# osmo-bts-lna.net
KiCad netlist of a schematic drawn in EAGLE
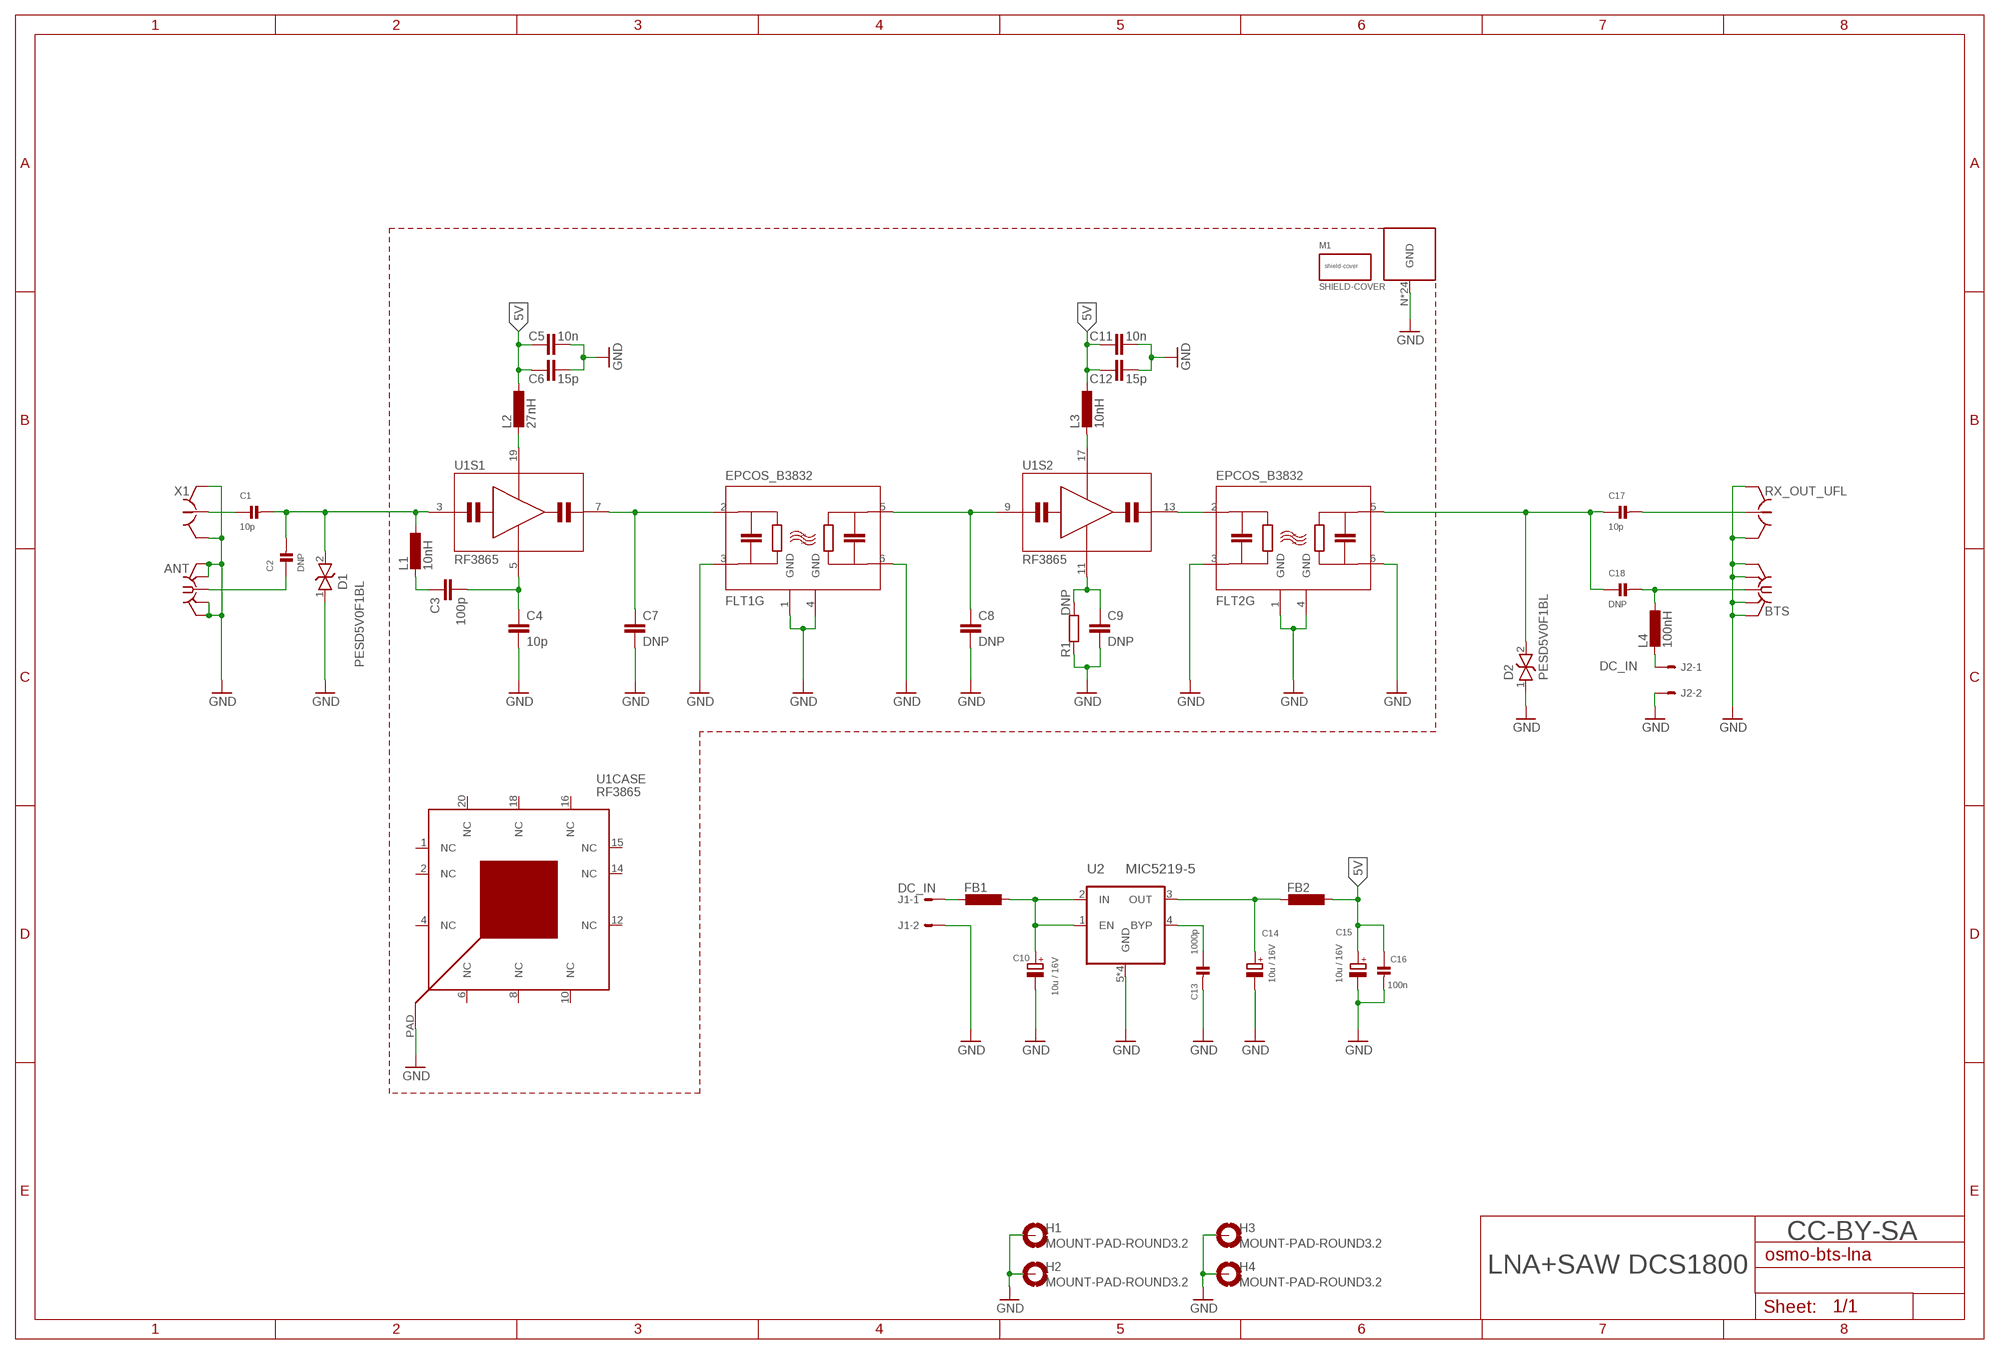
[diagram p0: schematic, sheet 1]

(export (version "E")
  (design (tool "Eeschema 10.0.6"))
  (components
    (comp (ref "ANT")
      (value "SMA-F-S-EDGE")
      (footprint "eagle-import:SMA-F-S-EDGE")
      (description "NO DESCRIPTION")
      (fields
        (field (name "MANUFACTURER") "UNKNOWN MANUFACTURER")
        (field (name "MANUFACTURERPARTNUMBER") "UNKNOWN MANUFACTURER PART NUMBER")
      )
      (libsource (lib "eagle-import") (part "SMA-F-S-EDGE"))
    )
    (comp (ref "BTS")
      (value "SMA-F-S-EDGE")
      (footprint "eagle-import:SMA-F-S-EDGE")
      (description "NO DESCRIPTION")
      (fields
        (field (name "MANUFACTURER") "UNKNOWN MANUFACTURER")
        (field (name "MANUFACTURERPARTNUMBER") "UNKNOWN MANUFACTURER PART NUMBER")
      )
      (libsource (lib "eagle-import") (part "SMA-F-S-EDGE"))
    )
    (comp (ref "C1")
      (value "10p")
      (footprint "eagle-import:_0603")
      (description "CAP CER 10PF 50V C0G/NP0 0603")
      (fields
        (field (name "MANUFACTURER") "KEMET")
        (field (name "MANUFACTURERPARTNUMBER") "C0603C100J5GACTU")
      )
      (libsource (lib "eagle-import") (part "CAP_CERAMIC_0603"))
    )
    (comp (ref "C2")
      (value "DNP")
      (footprint "eagle-import:_0603")
      (description "NO DESCRIPTION")
      (fields
        (field (name "MANUFACTURER") "UNKNOWN MANUFACTURER")
        (field (name "MANUFACTURERPARTNUMBER") "UNKNOWN MANUFACTURER PART NUMBER")
      )
      (libsource (lib "eagle-import") (part "CAP_CERAMIC_0603"))
    )
    (comp (ref "C3")
      (value "100p")
      (footprint "eagle-import:0603")
      (description "CAP CER 100PF 50V C0G/NP0 0603")
      (fields
        (field (name "MANUFACTURER") "AVX Corporation")
        (field (name "MANUFACTURERPARTNUMBER") "06035A101FAT2A")
      )
      (libsource (lib "eagle-import") (part "C-EU_0603"))
    )
    (comp (ref "C4")
      (value "10p")
      (footprint "eagle-import:0603")
      (description "CAP CER 10PF 50V C0G/NP0 0603")
      (fields
        (field (name "MANUFACTURER") "KEMET")
        (field (name "MANUFACTURERPARTNUMBER") "C0603C100J5GACTU")
      )
      (libsource (lib "eagle-import") (part "C-EU_0603"))
    )
    (comp (ref "C5")
      (value "10n")
      (footprint "eagle-import:0603")
      (description "CAP CER 10000PF 100V X7R 0603")
      (fields
        (field (name "MANUFACTURER") "Murata Electronics North America")
        (field (name "MANUFACTURERPARTNUMBER") "GCM188R72A103KA37D")
      )
      (libsource (lib "eagle-import") (part "C-EU_0603"))
    )
    (comp (ref "C6")
      (value "15p")
      (footprint "eagle-import:0603")
      (description "CAP CER 15PF 50V C0G/NP0 0603")
      (fields
        (field (name "MANUFACTURER") "Samsung Electro-Mechanics")
        (field (name "MANUFACTURERPARTNUMBER") "CL10C150JB8NCNC")
      )
      (libsource (lib "eagle-import") (part "C-EU_0603"))
    )
    (comp (ref "C7")
      (value "DNP")
      (footprint "eagle-import:0603")
      (description "NO DESCRIPTION")
      (fields
        (field (name "MANUFACTURER") "UNKNOWN MANUFACTURER")
        (field (name "MANUFACTURERPARTNUMBER") "UNKNOWN MANUFACTURER PART NUMBER")
      )
      (libsource (lib "eagle-import") (part "C-EU_0603"))
    )
    (comp (ref "C8")
      (value "DNP")
      (footprint "eagle-import:0603")
      (description "NO DESCRIPTION")
      (fields
        (field (name "MANUFACTURER") "UNKNOWN MANUFACTURER")
        (field (name "MANUFACTURERPARTNUMBER") "UNKNOWN MANUFACTURER PART NUMBER")
      )
      (libsource (lib "eagle-import") (part "C-EU_0603"))
    )
    (comp (ref "C9")
      (value "DNP")
      (footprint "eagle-import:0603")
      (description "NO DESCRIPTION")
      (fields
        (field (name "MANUFACTURER") "UNKNOWN MANUFACTURER")
        (field (name "MANUFACTURERPARTNUMBER") "UNKNOWN MANUFACTURER PART NUMBER")
      )
      (libsource (lib "eagle-import") (part "C-EU_0603"))
    )
    (comp (ref "C10")
      (value "10u / 16V")
      (footprint "eagle-import:CPOL1206")
      (description "CAP CER 10UF 16V X5R 0805")
      (fields
        (field (name "MANUFACTURER") "Samsung Electro-Mechanics")
        (field (name "MANUFACTURERPARTNUMBER") "CL21A106KOCLRNC")
      )
      (libsource (lib "eagle-import") (part "CPOL-EU-1206"))
    )
    (comp (ref "C11")
      (value "10n")
      (footprint "eagle-import:0603")
      (description "CAP CER 10000PF 100V X7R 0603")
      (fields
        (field (name "MANUFACTURER") "Murata Electronics North America")
        (field (name "MANUFACTURERPARTNUMBER") "GCM188R72A103KA37D")
      )
      (libsource (lib "eagle-import") (part "C-EU_0603"))
    )
    (comp (ref "C12")
      (value "15p")
      (footprint "eagle-import:0603")
      (description "CAP CER 15PF 50V C0G/NP0 0603")
      (fields
        (field (name "MANUFACTURER") "Samsung Electro-Mechanics")
        (field (name "MANUFACTURERPARTNUMBER") "CL10C150JB8NCNC")
      )
      (libsource (lib "eagle-import") (part "C-EU_0603"))
    )
    (comp (ref "C13")
      (value "1000p")
      (footprint "eagle-import:_0603")
      (description "CAP CER 1000PF 16V 10% X7R 0402")
      (fields
        (field (name "MANUFACTURER") "Yageo")
        (field (name "MANUFACTURERPARTNUMBER") "CC0402KRX7R7BB102")
      )
      (libsource (lib "eagle-import") (part "CAP_CERAMIC_0603"))
    )
    (comp (ref "C14")
      (value "10u / 16V")
      (footprint "eagle-import:CPOL1206")
      (description "CAP CER 10UF 16V X5R 0805")
      (fields
        (field (name "MANUFACTURER") "Samsung Electro-Mechanics")
        (field (name "MANUFACTURERPARTNUMBER") "CL21A106KOCLRNC")
      )
      (libsource (lib "eagle-import") (part "CPOL-EU-1206"))
    )
    (comp (ref "C15")
      (value "10u / 16V")
      (footprint "eagle-import:CPOL1206")
      (description "CAP CER 10UF 16V X5R 0805")
      (fields
        (field (name "MANUFACTURER") "Samsung Electro-Mechanics")
        (field (name "MANUFACTURERPARTNUMBER") "CL21A106KOCLRNC")
      )
      (libsource (lib "eagle-import") (part "CPOL-EU-1206"))
    )
    (comp (ref "C16")
      (value "100n")
      (footprint "eagle-import:_0603")
      (description "CAP CER 0.1UF 16V X7R 0603")
      (fields
        (field (name "MANUFACTURER") "Samsung Electro-Mechanics")
        (field (name "MANUFACTURERPARTNUMBER") "CL10B104KO8NNNC")
      )
      (libsource (lib "eagle-import") (part "CAP_CERAMIC_0603"))
    )
    (comp (ref "C17")
      (value "10p")
      (footprint "eagle-import:_0603")
      (description "CAP CER 10PF 50V C0G/NP0 0603")
      (fields
        (field (name "MANUFACTURER") "KEMET")
        (field (name "MANUFACTURERPARTNUMBER") "C0603C100J5GACTU")
      )
      (libsource (lib "eagle-import") (part "CAP_CERAMIC_0603"))
    )
    (comp (ref "C18")
      (value "DNP")
      (footprint "eagle-import:_0603")
      (description "NO DESCRIPTION")
      (fields
        (field (name "MANUFACTURER") "UNKNOWN MANUFACTURER")
        (field (name "MANUFACTURERPARTNUMBER") "UNKNOWN MANUFACTURER PART NUMBER")
      )
      (libsource (lib "eagle-import") (part "CAP_CERAMIC_0603"))
    )
    (comp (ref "D1")
      (value "PESD5V0F1BL")
      (footprint "eagle-import:SOD882")
      (description "TVS DIODE 5.5V 15V SOD882")
      (fields
        (field (name "MANUFACTURER") "Nexperia USA Inc.")
        (field (name "MANUFACTURERPARTNUMBER") "PESD5V0F1BL,315")
      )
      (libsource (lib "eagle-import") (part "D_ESD_SOD882"))
    )
    (comp (ref "D2")
      (value "PESD5V0F1BL")
      (footprint "eagle-import:SOD882")
      (description "TVS DIODE 5.5V 15V SOD882")
      (fields
        (field (name "MANUFACTURER") "Nexperia USA Inc.")
        (field (name "MANUFACTURERPARTNUMBER") "PESD5V0F1BL,315")
      )
      (libsource (lib "eagle-import") (part "D_ESD_SOD882"))
    )
    (comp (ref "FB1")
      (value "FBEAD_1206")
      (footprint "eagle-import:1206")
      (description "FERRITE BEAD 1 KOHM 0805 1LN")
      (fields
        (field (name "MANUFACTURER") "Laird-Signal Integrity Products")
        (field (name "MANUFACTURERPARTNUMBER") "HZ0805D102R-10")
      )
      (libsource (lib "eagle-import") (part "FBEAD_1206"))
    )
    (comp (ref "FB2")
      (value "INDUCTOR0603")
      (footprint "eagle-import:0603")
      (description "FERRITE BEAD 1 KOHM 0805 1LN")
      (fields
        (field (name "MANUFACTURER") "Laird-Signal Integrity Products")
        (field (name "MANUFACTURERPARTNUMBER") "HZ0805D102R-10")
      )
      (libsource (lib "eagle-import") (part "INDUCTOR0603"))
    )
    (comp (ref "FLT1")
      (value "EPCOS_B3832")
      (footprint "eagle-import:DCC6C")
      (description "NO DESCRIPTION")
      (fields
        (field (name "CLASS") "UNKNOWN CLASS")
        (field (name "LINK") "UNKNOWN LINK")
        (field (name "MANUFACTURER") "UNKNOWN MANUFACTURER")
        (field (name "MANUFACTURERPARTNUMBER") "UNKNOWN MANUFACTURER PART NUMBER")
        (field (name "POPULATED") "TRUE")
        (field (name "ROHSCERTIFICATE") "UNKNOWN ROHS CERTIFICATE")
        (field (name "SOURCE") "UNKNOWN SOURCE")
        (field (name "SOURCEPARTNUMBER") "UNKNOWN SOURCE PART NUMBER")
      )
      (libsource (lib "eagle-import") (part "EPCOS_B3832"))
    )
    (comp (ref "FLT2")
      (value "EPCOS_B3832")
      (footprint "eagle-import:DCC6C")
      (description "NO DESCRIPTION")
      (fields
        (field (name "CLASS") "UNKNOWN CLASS")
        (field (name "LINK") "UNKNOWN LINK")
        (field (name "MANUFACTURER") "UNKNOWN MANUFACTURER")
        (field (name "MANUFACTURERPARTNUMBER") "UNKNOWN MANUFACTURER PART NUMBER")
        (field (name "POPULATED") "TRUE")
        (field (name "ROHSCERTIFICATE") "UNKNOWN ROHS CERTIFICATE")
        (field (name "SOURCE") "UNKNOWN SOURCE")
        (field (name "SOURCEPARTNUMBER") "UNKNOWN SOURCE PART NUMBER")
      )
      (libsource (lib "eagle-import") (part "EPCOS_B3832"))
    )
    (comp (ref "H1")
      (value "MOUNT-PAD-ROUND3.2")
      (footprint "eagle-import:3,2-PAD")
      (description "NO DESCRIPTION")
      (fields
        (field (name "MANUFACTURER") "UNKNOWN MANUFACTURER")
        (field (name "MANUFACTURERPARTNUMBER") "UNKNOWN MANUFACTURER PART NUMBER")
      )
      (libsource (lib "eagle-import") (part "MOUNT-PAD-ROUND3.2"))
    )
    (comp (ref "H2")
      (value "MOUNT-PAD-ROUND3.2")
      (footprint "eagle-import:3,2-PAD")
      (description "NO DESCRIPTION")
      (fields
        (field (name "MANUFACTURER") "UNKNOWN MANUFACTURER")
        (field (name "MANUFACTURERPARTNUMBER") "UNKNOWN MANUFACTURER PART NUMBER")
      )
      (libsource (lib "eagle-import") (part "MOUNT-PAD-ROUND3.2"))
    )
    (comp (ref "H3")
      (value "MOUNT-PAD-ROUND3.2")
      (footprint "eagle-import:3,2-PAD")
      (description "NO DESCRIPTION")
      (fields
        (field (name "MANUFACTURER") "UNKNOWN MANUFACTURER")
        (field (name "MANUFACTURERPARTNUMBER") "UNKNOWN MANUFACTURER PART NUMBER")
      )
      (libsource (lib "eagle-import") (part "MOUNT-PAD-ROUND3.2"))
    )
    (comp (ref "H4")
      (value "MOUNT-PAD-ROUND3.2")
      (footprint "eagle-import:3,2-PAD")
      (description "NO DESCRIPTION")
      (fields
        (field (name "MANUFACTURER") "UNKNOWN MANUFACTURER")
        (field (name "MANUFACTURERPARTNUMBER") "UNKNOWN MANUFACTURER PART NUMBER")
      )
      (libsource (lib "eagle-import") (part "MOUNT-PAD-ROUND3.2"))
    )
    (comp (ref "J1")
      (value "DC_IN")
      (footprint "eagle-import:6410-02")
      (description "NO DESCRIPTION")
      (fields
        (field (name "MANUFACTURER") "UNKNOWN MANUFACTURER")
        (field (name "MANUFACTURERPARTNUMBER") "UNKNOWN MANUFACTURER PART NUMBER")
        (field (name "CLASS") "CONNECTOR\\JUMPER")
        (field (name "LINK") "UNKNOWN LINK")
        (field (name "POPULATED") "TRUE")
        (field (name "ROHSCERTIFICATE") "UNKNOWN ROHS CERTIFICATE")
        (field (name "SOURCE") "UNKNOWN SOURCE")
        (field (name "SOURCEPARTNUMBER") "UNKNOWN SOURCE PART NUMBER")
      )
      (libsource (lib "eagle-import") (part "22-?-0227-2021"))
    )
    (comp (ref "J2")
      (value "DC_IN")
      (footprint "eagle-import:6410-02")
      (description "NO DESCRIPTION")
      (fields
        (field (name "MANUFACTURER") "UNKNOWN MANUFACTURER")
        (field (name "MANUFACTURERPARTNUMBER") "UNKNOWN MANUFACTURER PART NUMBER")
        (field (name "CLASS") "CONNECTOR\\JUMPER")
        (field (name "LINK") "UNKNOWN LINK")
        (field (name "POPULATED") "TRUE")
        (field (name "ROHSCERTIFICATE") "UNKNOWN ROHS CERTIFICATE")
        (field (name "SOURCE") "UNKNOWN SOURCE")
        (field (name "SOURCEPARTNUMBER") "UNKNOWN SOURCE PART NUMBER")
      )
      (libsource (lib "eagle-import") (part "22-?-0227-2021"))
    )
    (comp (ref "L1")
      (value "10nH")
      (footprint "eagle-import:0603")
      (description "FIXED IND 10NH 700MA 130 MOHM")
      (fields
        (field (name "MANUFACTURER") "Bourns Inc.")
        (field (name "MANUFACTURERPARTNUMBER") "PM0603-10NJ-RC")
      )
      (libsource (lib "eagle-import") (part "L-EU_0603"))
    )
    (comp (ref "L2")
      (value "27nH")
      (footprint "eagle-import:0603")
      (description "FIXED IND 27NH 600MA 220 MOHM")
      (fields
        (field (name "MANUFACTURER") "Bourns Inc.")
        (field (name "MANUFACTURERPARTNUMBER") "PM0603-27NJ-RC")
      )
      (libsource (lib "eagle-import") (part "L-EU_0603"))
    )
    (comp (ref "L3")
      (value "10nH")
      (footprint "eagle-import:0603")
      (description "FIXED IND 10NH 700MA 130 MOHM")
      (fields
        (field (name "MANUFACTURER") "Bourns Inc.")
        (field (name "MANUFACTURERPARTNUMBER") "PM0603-10NJ-RC")
      )
      (libsource (lib "eagle-import") (part "L-EU_0603"))
    )
    (comp (ref "L4")
      (value "100nH")
      (footprint "eagle-import:_0402")
      (description "FIXED IND 100NH 500MA 1.25 OHM")
      (fields
        (field (name "MANUFACTURER") "Murata Electronics North America")
        (field (name "MANUFACTURERPARTNUMBER") "LQG15HHR10J02D")
      )
      (libsource (lib "eagle-import") (part "INDUCTOR_0402"))
    )
    (comp (ref "R1")
      (value "DNP")
      (footprint "eagle-import:0603")
      (description "NO DESCRIPTION")
      (fields
        (field (name "MANUFACTURER") "UNKNOWN MANUFACTURER")
        (field (name "MANUFACTURERPARTNUMBER") "UNKNOWN MANUFACTURER PART NUMBER")
      )
      (libsource (lib "eagle-import") (part "R-EU_0603"))
    )
    (comp (ref "RX_OUT_UFL")
      (value "HRS_UFL")
      (footprint "eagle-import:HRS_UFL")
      (description "CONN U.FL RCPT STR 50 OHM SMD")
      (fields
        (field (name "MANUFACTURER") "Hirose Electric Co Ltd")
        (field (name "MANUFACTURERPARTNUMBER") "U.FL-R-SMT(01)")
      )
      (libsource (lib "eagle-import") (part "HRS_UFL"))
    )
    (comp (ref "SHLD1")
      (value "SHIELD-BMI-S-204")
      (footprint "eagle-import:BMI-S-204")
      (description "BOARD SHIELD 1.26X1.26\" FRAME")
      (fields
        (field (name "MANUFACTURER") "Laird Technologies EMI")
        (field (name "MANUFACTURERPARTNUMBER") "BMI-S-204-F")
      )
      (libsource (lib "eagle-import") (part "SHIELD-BMI-S-204"))
    )
    (comp (ref "U1")
      (value "RF3865")
      (footprint "eagle-import:QFN20_5X5_PAD")
      (description "NO DESCRIPTION")
      (fields
        (field (name "MANUFACTURER") "UNKNOWN MANUFACTURER")
        (field (name "MANUFACTURERPARTNUMBER") "UNKNOWN MANUFACTURER PART NUMBER")
        (field (name "CLASS") "IC")
        (field (name "LINK") "UNKNOWN LINK")
        (field (name "POPULATED") "TRUE")
        (field (name "ROHSCERTIFICATE") "UNKNOWN ROHS CERTIFICATE")
        (field (name "SOURCE") "UNKNOWN SOURCE")
        (field (name "SOURCEPARTNUMBER") "UNKNOWN SOURCE PART NUMBER")
      )
      (libsource (lib "eagle-import") (part "RF3865"))
    )
    (comp (ref "U2")
      (value "MIC5219-5")
      (footprint "eagle-import:MSOP8")
      (description "IC REG LINEAR 5V 500MA 8MSOP")
      (fields
        (field (name "MANUFACTURER") "Microchip Technology")
        (field (name "MANUFACTURERPARTNUMBER") "MIC5219-5.0YMM")
      )
      (libsource (lib "eagle-import") (part "MIC5219FMM8"))
    )
    (comp (ref "X1")
      (value "HRS_UFL")
      (footprint "eagle-import:HRS_UFL")
      (description "CONN U.FL RCPT STR 50 OHM SMD")
      (fields
        (field (name "MANUFACTURER") "Hirose Electric Co Ltd")
        (field (name "MANUFACTURERPARTNUMBER") "U.FL-R-SMT(01)")
      )
      (libsource (lib "eagle-import") (part "HRS_UFL"))
    )
  )
  (nets
    (net (code "1") (name "5V") (class "Default")
      (node (ref "C11") (pin "1") (pinfunction "1_1") (pintype "passive"))
      (node (ref "C12") (pin "1") (pinfunction "1_1") (pintype "passive"))
      (node (ref "C15") (pin "+") (pinfunction "+_+") (pintype "passive"))
      (node (ref "C16") (pin "1") (pinfunction "1_1") (pintype "passive"))
      (node (ref "C5") (pin "1") (pinfunction "1_1") (pintype "passive"))
      (node (ref "C6") (pin "1") (pinfunction "1_1") (pintype "passive"))
      (node (ref "FB2") (pin "2") (pinfunction "2_2") (pintype "passive"))
      (node (ref "L2") (pin "1") (pinfunction "1_1") (pintype "passive"))
      (node (ref "L3") (pin "1") (pinfunction "1_1") (pintype "passive"))
    )
    (net (code "2") (name "GND") (class "Default")
      (node (ref "ANT") (pin "BG1") (pinfunction "GND_BG1") (pintype "power_in"))
      (node (ref "ANT") (pin "BG2") (pinfunction "GND_BG2") (pintype "power_in"))
      (node (ref "ANT") (pin "TG1") (pinfunction "GND_TG1") (pintype "power_in"))
      (node (ref "ANT") (pin "TG2") (pinfunction "GND_TG2") (pintype "power_in"))
      (node (ref "BTS") (pin "BG1") (pinfunction "GND_BG1") (pintype "power_in"))
      (node (ref "BTS") (pin "BG2") (pinfunction "GND_BG2") (pintype "power_in"))
      (node (ref "BTS") (pin "TG1") (pinfunction "GND_TG1") (pintype "power_in"))
      (node (ref "BTS") (pin "TG2") (pinfunction "GND_TG2") (pintype "power_in"))
      (node (ref "C10") (pin "-") (pinfunction "-_-") (pintype "passive"))
      (node (ref "C11") (pin "2") (pinfunction "2_2") (pintype "passive"))
      (node (ref "C12") (pin "2") (pinfunction "2_2") (pintype "passive"))
      (node (ref "C13") (pin "2") (pinfunction "2_2") (pintype "passive"))
      (node (ref "C14") (pin "-") (pinfunction "-_-") (pintype "passive"))
      (node (ref "C15") (pin "-") (pinfunction "-_-") (pintype "passive"))
      (node (ref "C16") (pin "2") (pinfunction "2_2") (pintype "passive"))
      (node (ref "C4") (pin "2") (pinfunction "2_2") (pintype "passive"))
      (node (ref "C5") (pin "2") (pinfunction "2_2") (pintype "passive"))
      (node (ref "C6") (pin "2") (pinfunction "2_2") (pintype "passive"))
      (node (ref "C7") (pin "2") (pinfunction "2_2") (pintype "passive"))
      (node (ref "C8") (pin "2") (pinfunction "2_2") (pintype "passive"))
      (node (ref "C9") (pin "2") (pinfunction "2_2") (pintype "passive"))
      (node (ref "D1") (pin "1") (pinfunction "1_1") (pintype "passive"))
      (node (ref "D2") (pin "1") (pinfunction "1_1") (pintype "passive"))
      (node (ref "FLT1") (pin "1") (pinfunction "GND_1") (pintype "power_in"))
      (node (ref "FLT1") (pin "3") (pinfunction "IN_GND_3") (pintype "passive"))
      (node (ref "FLT1") (pin "4") (pinfunction "GND_4") (pintype "power_in"))
      (node (ref "FLT1") (pin "6") (pinfunction "OUT_GND_6") (pintype "passive"))
      (node (ref "FLT2") (pin "1") (pinfunction "GND_1") (pintype "power_in"))
      (node (ref "FLT2") (pin "3") (pinfunction "IN_GND_3") (pintype "passive"))
      (node (ref "FLT2") (pin "4") (pinfunction "GND_4") (pintype "power_in"))
      (node (ref "FLT2") (pin "6") (pinfunction "OUT_GND_6") (pintype "passive"))
      (node (ref "H1") (pin "B3,2") (pinfunction "MOUNT_B3,2") (pintype "passive"))
      (node (ref "H2") (pin "B3,2") (pinfunction "MOUNT_B3,2") (pintype "passive"))
      (node (ref "H3") (pin "B3,2") (pinfunction "MOUNT_B3,2") (pintype "passive"))
      (node (ref "H4") (pin "B3,2") (pinfunction "MOUNT_B3,2") (pintype "passive"))
      (node (ref "J1") (pin "2") (pinfunction "S_2") (pintype "passive"))
      (node (ref "J2") (pin "2") (pinfunction "S_2") (pintype "passive"))
      (node (ref "R1") (pin "1") (pinfunction "1_1") (pintype "passive"))
      (node (ref "RX_OUT_UFL") (pin "GND@1") (pinfunction "GND_GND@1") (pintype "power_in"))
      (node (ref "RX_OUT_UFL") (pin "GND@2") (pinfunction "GND_GND@2") (pintype "power_in"))
      (node (ref "SHLD1") (pin "N") (pinfunction "GND_N") (pintype "bidirectional"))
      (node (ref "SHLD1") (pin "NNE") (pinfunction "GND_NNE") (pintype "bidirectional"))
      (node (ref "SHLD1") (pin "NNE1") (pinfunction "GND_NNE1") (pintype "bidirectional"))
      (node (ref "SHLD1") (pin "NNE2") (pinfunction "GND_NNE2") (pintype "bidirectional"))
      (node (ref "SHLD1") (pin "NNE4") (pinfunction "GND_NNE4") (pintype "bidirectional"))
      (node (ref "SHLD1") (pin "NNE5") (pinfunction "GND_NNE5") (pintype "bidirectional"))
      (node (ref "SHLD1") (pin "NNW") (pinfunction "GND_NNW") (pintype "bidirectional"))
      (node (ref "SHLD1") (pin "S") (pinfunction "GND_S") (pintype "bidirectional"))
      (node (ref "SHLD1") (pin "S1") (pinfunction "GND_S1") (pintype "bidirectional"))
      (node (ref "SHLD1") (pin "S2") (pinfunction "GND_S2") (pintype "bidirectional"))
      (node (ref "SHLD1") (pin "S3") (pinfunction "GND_S3") (pintype "bidirectional"))
      (node (ref "SHLD1") (pin "S4") (pinfunction "GND_S4") (pintype "bidirectional"))
      (node (ref "SHLD1") (pin "S5") (pinfunction "GND_S5") (pintype "bidirectional"))
      (node (ref "SHLD1") (pin "S6") (pinfunction "GND_S6") (pintype "bidirectional"))
      (node (ref "SHLD1") (pin "S7") (pinfunction "GND_S7") (pintype "bidirectional"))
      (node (ref "SHLD1") (pin "S8") (pinfunction "GND_S8") (pintype "bidirectional"))
      (node (ref "SHLD1") (pin "S9") (pinfunction "GND_S9") (pintype "bidirectional"))
      (node (ref "SHLD1") (pin "SSE") (pinfunction "GND_SSE") (pintype "bidirectional"))
      (node (ref "SHLD1") (pin "SSW") (pinfunction "GND_SSW") (pintype "bidirectional"))
      (node (ref "SHLD1") (pin "SSW1") (pinfunction "GND_SSW1") (pintype "bidirectional"))
      (node (ref "SHLD1") (pin "SSW2") (pinfunction "GND_SSW2") (pintype "bidirectional"))
      (node (ref "SHLD1") (pin "SSW3") (pinfunction "GND_SSW3") (pintype "bidirectional"))
      (node (ref "SHLD1") (pin "SSW4") (pinfunction "GND_SSW4") (pintype "bidirectional"))
      (node (ref "SHLD1") (pin "SSW5") (pinfunction "GND_SSW5") (pintype "bidirectional"))
      (node (ref "U1") (pin "PAD") (pinfunction "CASE_GND_PAD") (pintype "power_in"))
      (node (ref "U2") (pin "5") (pinfunction "GND_5") (pintype "power_in"))
      (node (ref "U2") (pin "6") (pinfunction "GND_6") (pintype "power_in"))
      (node (ref "U2") (pin "7") (pinfunction "GND_7") (pintype "power_in"))
      (node (ref "U2") (pin "8") (pinfunction "GND_8") (pintype "power_in"))
      (node (ref "X1") (pin "GND@1") (pinfunction "GND_GND@1") (pintype "power_in"))
      (node (ref "X1") (pin "GND@2") (pinfunction "GND_GND@2") (pintype "power_in"))
    )
    (net (code "3") (name "Net-(ANT-1)") (class "Default")
      (node (ref "ANT") (pin "C") (pinfunction "1_C") (pintype "passive"))
      (node (ref "C2") (pin "1") (pinfunction "1_1") (pintype "passive"))
    )
    (net (code "4") (name "Net-(BTS-1)") (class "Default")
      (node (ref "BTS") (pin "C") (pinfunction "1_C") (pintype "passive"))
      (node (ref "C18") (pin "2") (pinfunction "2_2") (pintype "passive"))
      (node (ref "L4") (pin "1") (pinfunction "1_1") (pintype "passive"))
    )
    (net (code "5") (name "Net-(C3-Pad1)") (class "Default")
      (node (ref "C3") (pin "1") (pinfunction "1_1") (pintype "passive"))
      (node (ref "L1") (pin "2") (pinfunction "2_2") (pintype "passive"))
    )
    (net (code "6") (name "Net-(FLT1B-IN)") (class "Default")
      (node (ref "C7") (pin "1") (pinfunction "1_1") (pintype "passive"))
      (node (ref "FLT1") (pin "2") (pinfunction "IN_2") (pintype "passive"))
      (node (ref "U1") (pin "7") (pinfunction "RF_OUT_7") (pintype "bidirectional"))
    )
    (net (code "7") (name "Net-(FLT1B-OUT)") (class "Default")
      (node (ref "C8") (pin "1") (pinfunction "1_1") (pintype "passive"))
      (node (ref "FLT1") (pin "5") (pinfunction "OUT_5") (pintype "passive"))
      (node (ref "U1") (pin "9") (pinfunction "RF_IN_9") (pintype "bidirectional"))
    )
    (net (code "8") (name "Net-(FLT2B-IN)") (class "Default")
      (node (ref "FLT2") (pin "2") (pinfunction "IN_2") (pintype "passive"))
      (node (ref "U1") (pin "13") (pinfunction "RF_OUT_13") (pintype "bidirectional"))
    )
    (net (code "9") (name "Net-(FLT2B-OUT)") (class "Default")
      (node (ref "C17") (pin "1") (pinfunction "1_1") (pintype "passive"))
      (node (ref "C18") (pin "1") (pinfunction "1_1") (pintype "passive"))
      (node (ref "D2") (pin "2") (pinfunction "2_2") (pintype "passive"))
      (node (ref "FLT2") (pin "5") (pinfunction "OUT_5") (pintype "passive"))
    )
    (net (code "10") (name "Net-(J1A-S)") (class "Default")
      (node (ref "FB1") (pin "1") (pinfunction "1_1") (pintype "passive"))
      (node (ref "J1") (pin "1") (pinfunction "S_1") (pintype "passive"))
    )
    (net (code "11") (name "Net-(J2A-S)") (class "Default")
      (node (ref "J2") (pin "1") (pinfunction "S_1") (pintype "passive"))
      (node (ref "L4") (pin "2") (pinfunction "2_2") (pintype "passive"))
    )
    (net (code "12") (name "Net-(RX_OUT_UFL-1)") (class "Default")
      (node (ref "C17") (pin "2") (pinfunction "2_2") (pintype "passive"))
      (node (ref "RX_OUT_UFL") (pin "SIG") (pinfunction "1_SIG") (pintype "passive"))
    )
    (net (code "13") (name "Net-(U1B-AC_GND)") (class "Default")
      (node (ref "C3") (pin "2") (pinfunction "2_2") (pintype "passive"))
      (node (ref "C4") (pin "1") (pinfunction "1_1") (pintype "passive"))
      (node (ref "U1") (pin "5") (pinfunction "AC_GND_5") (pintype "bidirectional"))
    )
    (net (code "14") (name "Net-(U1B-RF_IN)") (class "Default")
      (node (ref "C1") (pin "2") (pinfunction "2_2") (pintype "passive"))
      (node (ref "C2") (pin "2") (pinfunction "2_2") (pintype "passive"))
      (node (ref "D1") (pin "2") (pinfunction "2_2") (pintype "passive"))
      (node (ref "L1") (pin "1") (pinfunction "1_1") (pintype "passive"))
      (node (ref "U1") (pin "3") (pinfunction "RF_IN_3") (pintype "bidirectional"))
    )
    (net (code "15") (name "Net-(U1B-VDD)") (class "Default")
      (node (ref "L2") (pin "2") (pinfunction "2_2") (pintype "passive"))
      (node (ref "U1") (pin "19") (pinfunction "VDD_19") (pintype "bidirectional"))
    )
    (net (code "16") (name "Net-(U1C-AC_GND)") (class "Default")
      (node (ref "C9") (pin "1") (pinfunction "1_1") (pintype "passive"))
      (node (ref "R1") (pin "2") (pinfunction "2_2") (pintype "passive"))
      (node (ref "U1") (pin "11") (pinfunction "AC_GND_11") (pintype "bidirectional"))
    )
    (net (code "17") (name "Net-(U1C-VDD)") (class "Default")
      (node (ref "L3") (pin "2") (pinfunction "2_2") (pintype "passive"))
      (node (ref "U1") (pin "17") (pinfunction "VDD_17") (pintype "bidirectional"))
    )
    (net (code "18") (name "Net-(U2-BYP)") (class "Default")
      (node (ref "C13") (pin "1") (pinfunction "1_1") (pintype "passive"))
      (node (ref "U2") (pin "4") (pinfunction "BYP_4") (pintype "passive"))
    )
    (net (code "19") (name "Net-(U2-EN)") (class "Default")
      (node (ref "C10") (pin "+") (pinfunction "+_+") (pintype "passive"))
      (node (ref "FB1") (pin "2") (pinfunction "2_2") (pintype "passive"))
      (node (ref "U2") (pin "1") (pinfunction "EN_1") (pintype "input"))
      (node (ref "U2") (pin "2") (pinfunction "IN_2") (pintype "power_in"))
    )
    (net (code "20") (name "Net-(U2-OUT)") (class "Default")
      (node (ref "C14") (pin "+") (pinfunction "+_+") (pintype "passive"))
      (node (ref "FB2") (pin "1") (pinfunction "1_1") (pintype "passive"))
      (node (ref "U2") (pin "3") (pinfunction "OUT_3") (pintype "passive"))
    )
    (net (code "21") (name "Net-(X1-1)") (class "Default")
      (node (ref "C1") (pin "1") (pinfunction "1_1") (pintype "passive"))
      (node (ref "X1") (pin "SIG") (pinfunction "1_SIG") (pintype "passive"))
    )
    (net (code "22") (name "unconnected-(U1A-NC-Pad1)") (class "Default")
      (node (ref "U1") (pin "1") (pinfunction "NC_1") (pintype "no_connect"))
    )
    (net (code "23") (name "unconnected-(U1A-NC-Pad2)") (class "Default")
      (node (ref "U1") (pin "2") (pinfunction "NC_2") (pintype "no_connect"))
    )
    (net (code "24") (name "unconnected-(U1A-NC-Pad4)") (class "Default")
      (node (ref "U1") (pin "4") (pinfunction "NC_4") (pintype "no_connect"))
    )
    (net (code "25") (name "unconnected-(U1A-NC-Pad6)") (class "Default")
      (node (ref "U1") (pin "6") (pinfunction "NC_6") (pintype "no_connect"))
    )
    (net (code "26") (name "unconnected-(U1A-NC-Pad8)") (class "Default")
      (node (ref "U1") (pin "8") (pinfunction "NC_8") (pintype "no_connect"))
    )
    (net (code "27") (name "unconnected-(U1A-NC-Pad10)") (class "Default")
      (node (ref "U1") (pin "10") (pinfunction "NC_10") (pintype "no_connect"))
    )
    (net (code "28") (name "unconnected-(U1A-NC-Pad12)") (class "Default")
      (node (ref "U1") (pin "12") (pinfunction "NC_12") (pintype "no_connect"))
    )
    (net (code "29") (name "unconnected-(U1A-NC-Pad14)") (class "Default")
      (node (ref "U1") (pin "14") (pinfunction "NC_14") (pintype "no_connect"))
    )
    (net (code "30") (name "unconnected-(U1A-NC-Pad15)") (class "Default")
      (node (ref "U1") (pin "15") (pinfunction "NC_15") (pintype "no_connect"))
    )
    (net (code "31") (name "unconnected-(U1A-NC-Pad16)") (class "Default")
      (node (ref "U1") (pin "16") (pinfunction "NC_16") (pintype "no_connect"))
    )
    (net (code "32") (name "unconnected-(U1A-NC-Pad18)") (class "Default")
      (node (ref "U1") (pin "18") (pinfunction "NC_18") (pintype "no_connect"))
    )
    (net (code "33") (name "unconnected-(U1A-NC-Pad20)") (class "Default")
      (node (ref "U1") (pin "20") (pinfunction "NC_20") (pintype "no_connect"))
    )
  )
)
